# AutonoeGingerBread3.net
KiCad netlist of a schematic drawn in EAGLE
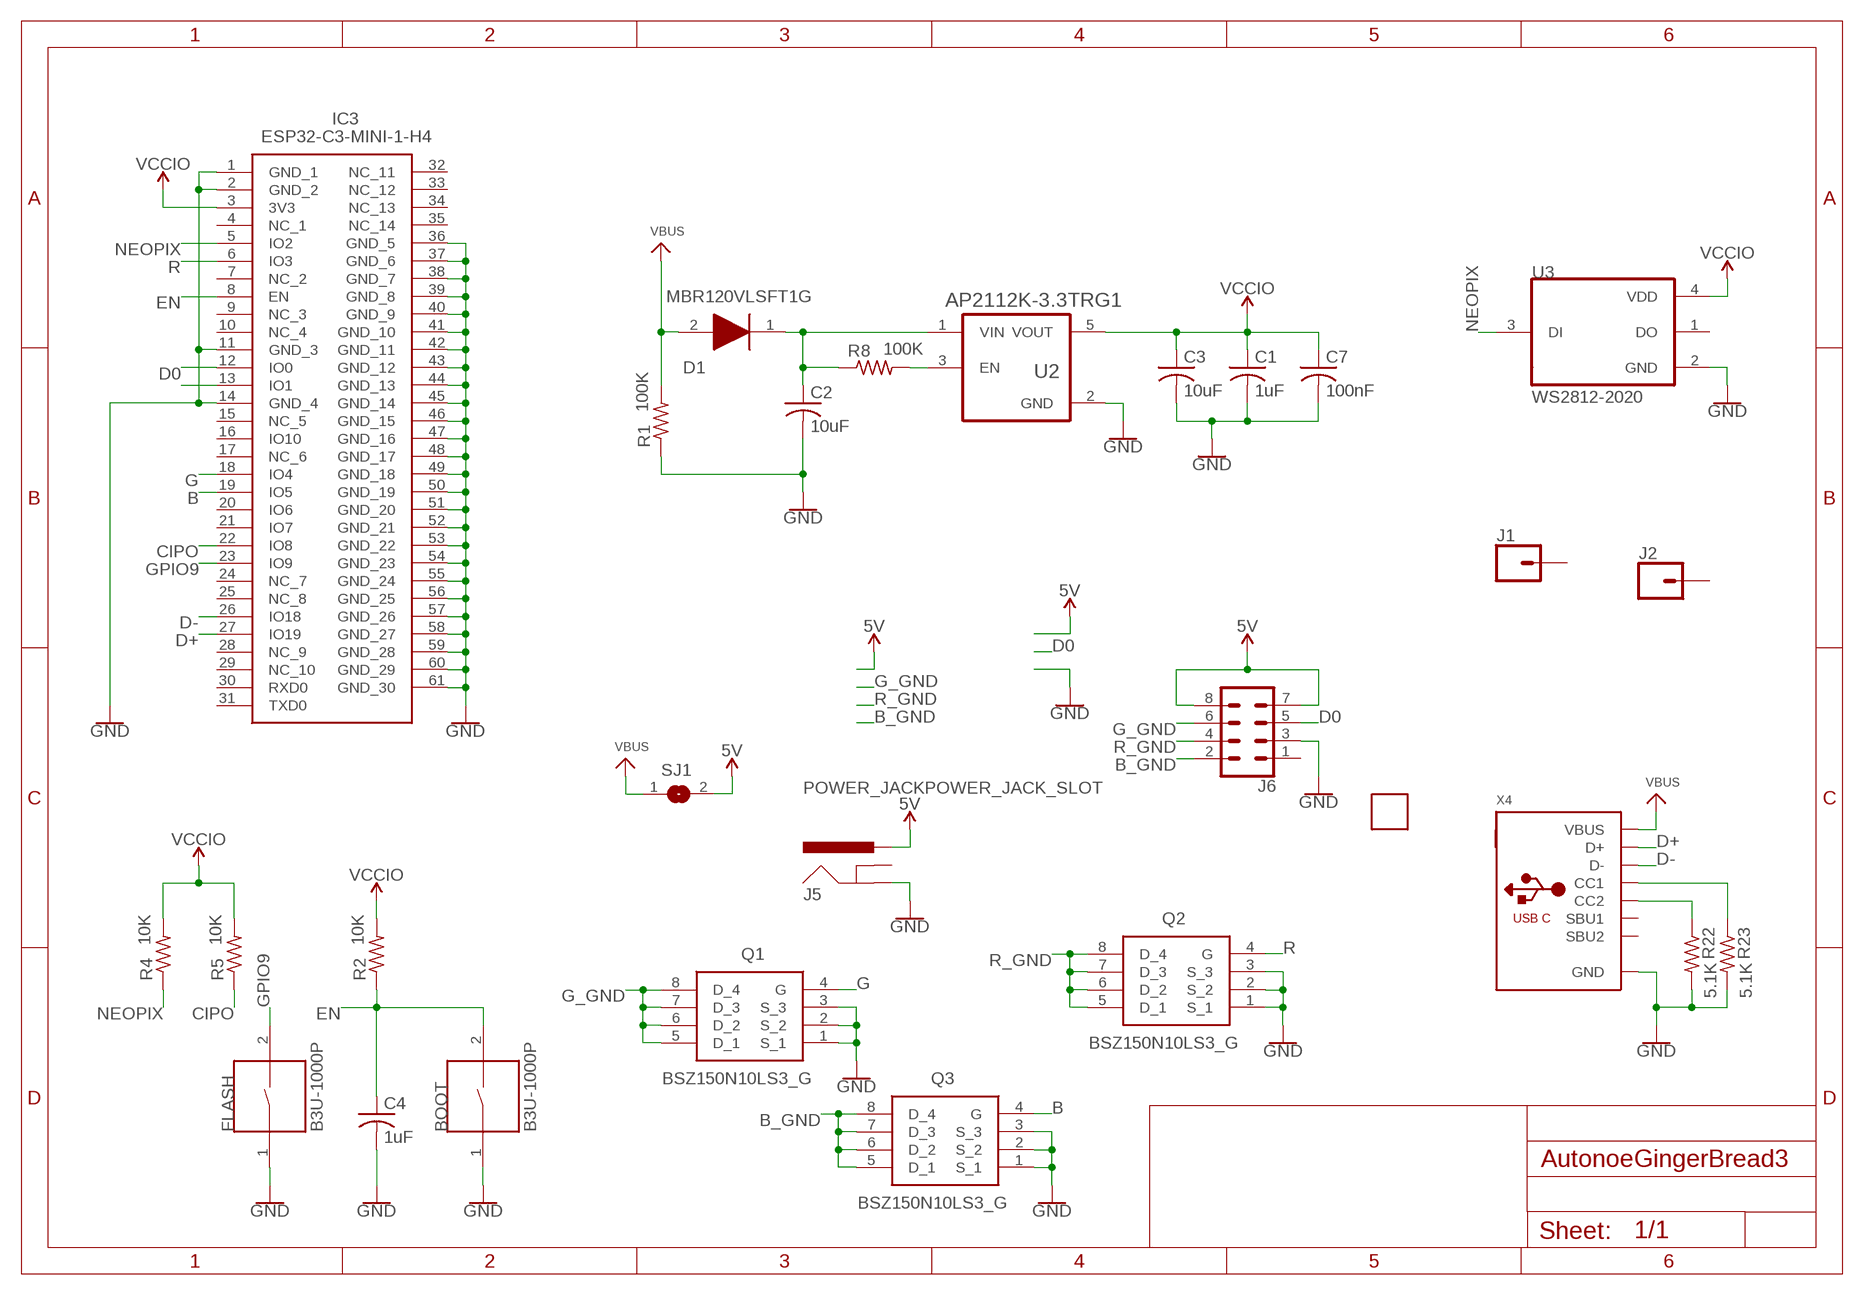
[diagram p0: schematic, sheet 1]

(export (version "E")
  (design (tool "Eeschema 10.0.6"))
  (components
    (comp (ref "BOOT")
      (value "B3U-1000P")
      (footprint "eagle-import:SW_B3U-1000P")
      (fields (field (name "MF") "Omron"))
      (libsource (lib "eagle-import") (part "B3U-1000P"))
    )
    (comp (ref "C1")
      (value "1uF")
      (footprint "eagle-import:C0402")
      (libsource (lib "eagle-import") (part "C-USC0402"))
    )
    (comp (ref "C2")
      (value "10uF")
      (footprint "eagle-import:C0402")
      (libsource (lib "eagle-import") (part "C-USC0402"))
    )
    (comp (ref "C3")
      (value "10uF")
      (footprint "eagle-import:C0402")
      (libsource (lib "eagle-import") (part "C-USC0402"))
    )
    (comp (ref "C4")
      (value "1uF")
      (footprint "eagle-import:C0402")
      (libsource (lib "eagle-import") (part "C-USC0402"))
    )
    (comp (ref "C7")
      (value "100nF")
      (footprint "eagle-import:C0402")
      (libsource (lib "eagle-import") (part "C-USC0402"))
    )
    (comp (ref "D1")
      (value "MBR120VLSFT1G")
      (footprint "eagle-import:SODFL3616X98N")
      (fields (field (name "MOUSER_PART_NUMBER") "863-MBR120VLSFT1G"))
      (libsource (lib "eagle-import") (part "MBR120VLSFT1G"))
    )
    (comp (ref "FLASH")
      (value "B3U-1000P")
      (footprint "eagle-import:SW_B3U-1000P")
      (fields (field (name "MF") "Omron"))
      (libsource (lib "eagle-import") (part "B3U-1000P"))
    )
    (comp (ref "IC3")
      (value "ESP32-C3-MINI-1-H4")
      (footprint "eagle-import:ESP32C3MINI1H4")
      (fields (field (name "MOUSER_PART_NUMBER") "356-ESP32-C3-MINI1H4"))
      (libsource (lib "eagle-import") (part "ESP32-C3-MINI-1-H4"))
    )
    (comp (ref "J1")
      (value "CONN_01PTH_2MM")
      (footprint "eagle-import:1X01_2MM")
      (libsource (lib "eagle-import") (part "CONN_01PTH_2MM"))
    )
    (comp (ref "J2")
      (value "CONN_01PTH_2MM")
      (footprint "eagle-import:1X01_2MM")
      (libsource (lib "eagle-import") (part "CONN_01PTH_2MM"))
    )
    (comp (ref "J5")
      (value "POWER_JACKPOWER_JACK_SLOT")
      (footprint "eagle-import:POWER_JACK_PTH_SLOT")
      (libsource (lib "eagle-import") (part "POWER_JACKPOWER_JACK_SLOT"))
    )
    (comp (ref "J6")
      (value "CONN_04X2")
      (footprint "eagle-import:2X4")
      (libsource (lib "eagle-import") (part "CONN_04X2"))
    )
    (comp (ref "Q1")
      (value "BSZ150N10LS3_G")
      (footprint "eagle-import:BSZ180P03NS3EGATMA1")
      (fields
        (field (name "MANUFACTURER_PART_NUMBER") "BSZ150N10LS3 G")
        (field (name "MOUSER_PART_NUMBER") "726-BSZ150N10LS3G")
      )
      (libsource (lib "eagle-import") (part "BSZ150N10LS3_G"))
    )
    (comp (ref "Q2")
      (value "BSZ150N10LS3_G")
      (footprint "eagle-import:BSZ180P03NS3EGATMA1")
      (fields
        (field (name "MANUFACTURER_PART_NUMBER") "BSZ150N10LS3 G")
        (field (name "MOUSER_PART_NUMBER") "726-BSZ150N10LS3G")
      )
      (libsource (lib "eagle-import") (part "BSZ150N10LS3_G"))
    )
    (comp (ref "Q3")
      (value "BSZ150N10LS3_G")
      (footprint "eagle-import:BSZ180P03NS3EGATMA1")
      (fields
        (field (name "MANUFACTURER_PART_NUMBER") "BSZ150N10LS3 G")
        (field (name "MOUSER_PART_NUMBER") "726-BSZ150N10LS3G")
      )
      (libsource (lib "eagle-import") (part "BSZ150N10LS3_G"))
    )
    (comp (ref "R1")
      (value "100K")
      (footprint "eagle-import:R0402")
      (libsource (lib "eagle-import") (part "R-US_R0402"))
    )
    (comp (ref "R2")
      (value "10K")
      (footprint "eagle-import:R0402")
      (libsource (lib "eagle-import") (part "R-US_R0402"))
    )
    (comp (ref "R4")
      (value "10K")
      (footprint "eagle-import:R0402")
      (libsource (lib "eagle-import") (part "R-US_R0402"))
    )
    (comp (ref "R5")
      (value "10K")
      (footprint "eagle-import:R0402")
      (libsource (lib "eagle-import") (part "R-US_R0402"))
    )
    (comp (ref "R8")
      (value "100K")
      (footprint "eagle-import:R0402")
      (libsource (lib "eagle-import") (part "R-US_R0402"))
    )
    (comp (ref "R22")
      (value "5.1K")
      (footprint "eagle-import:R0402")
      (libsource (lib "eagle-import") (part "R-US_R0402"))
    )
    (comp (ref "R23")
      (value "5.1K")
      (footprint "eagle-import:R0402")
      (libsource (lib "eagle-import") (part "R-US_R0402"))
    )
    (comp (ref "SJ1") (value "SJ") (footprint "eagle-import:SJ") (libsource (lib "eagle-import") (part "SJ")))
    (comp (ref "U$3")
      (value "SMARTT_SMALL")
      (footprint "eagle-import:SMARTT_SMALL")
      (libsource (lib "eagle-import") (part "SMARTT_SMALL"))
    )
    (comp (ref "U2")
      (value "AP2112K-3.3TRG1")
      (footprint "eagle-import:SOT95P285X140-5N")
      (fields (field (name "MF") "Diodes Inc."))
      (libsource (lib "eagle-import") (part "AP2112K-3.3TRG1"))
    )
    (comp (ref "U3")
      (value "WS2812-2020")
      (footprint "eagle-import:LED_WS2812-2020")
      (fields (field (name "MF") "Worldsemi"))
      (libsource (lib "eagle-import") (part "WS2812-2020"))
    )
    (comp (ref "X4")
      (value "MICROBUILDER_USB_C")
      (footprint "eagle-import:MICROBUILDER_USB_C_CUSB31-CFM2AX-01-X")
      (libsource (lib "eagle-import") (part "MICROBUILDER_USB_C"))
    )
  )
  (nets
    (net (code "1") (name "/B") (class "Default")
      (node (ref "IC3") (pin "19") (pinfunction "IO5_19") (pintype "bidirectional"))
      (node (ref "Q3") (pin "4") (pinfunction "G_4") (pintype "bidirectional"))
    )
    (net (code "2") (name "/B_GND") (class "Default")
      (node (ref "J6") (pin "2") (pinfunction "2_2") (pintype "passive"))
      (node (ref "Q3") (pin "5") (pinfunction "D_1_5") (pintype "bidirectional"))
      (node (ref "Q3") (pin "6") (pinfunction "D_2_6") (pintype "bidirectional"))
      (node (ref "Q3") (pin "7") (pinfunction "D_3_7") (pintype "bidirectional"))
      (node (ref "Q3") (pin "8") (pinfunction "D_4_8") (pintype "bidirectional"))
    )
    (net (code "3") (name "/CIPO") (class "Default")
      (node (ref "IC3") (pin "22") (pinfunction "IO8_22") (pintype "bidirectional"))
      (node (ref "R5") (pin "1") (pinfunction "1_1") (pintype "passive"))
    )
    (net (code "4") (name "/D+") (class "Default")
      (node (ref "IC3") (pin "27") (pinfunction "IO19_27") (pintype "bidirectional"))
      (node (ref "X4") (pin "A6") (pinfunction "D+_A6") (pintype "bidirectional"))
      (node (ref "X4") (pin "B6") (pinfunction "D+_B6") (pintype "bidirectional"))
    )
    (net (code "5") (name "/D-") (class "Default")
      (node (ref "IC3") (pin "26") (pinfunction "IO18_26") (pintype "bidirectional"))
      (node (ref "X4") (pin "A7") (pinfunction "D-_A7") (pintype "bidirectional"))
      (node (ref "X4") (pin "B7") (pinfunction "D-_B7") (pintype "bidirectional"))
    )
    (net (code "6") (name "/D0") (class "Default")
      (node (ref "IC3") (pin "12") (pinfunction "IO0_12") (pintype "bidirectional"))
      (node (ref "J6") (pin "5") (pinfunction "5_5") (pintype "passive"))
    )
    (net (code "7") (name "/EN") (class "Default")
      (node (ref "BOOT") (pin "2") (pinfunction "2_2") (pintype "passive"))
      (node (ref "C4") (pin "1") (pinfunction "1_1") (pintype "passive"))
      (node (ref "IC3") (pin "8") (pinfunction "EN_8") (pintype "bidirectional"))
      (node (ref "R2") (pin "1") (pinfunction "1_1") (pintype "passive"))
    )
    (net (code "8") (name "/G") (class "Default")
      (node (ref "IC3") (pin "18") (pinfunction "IO4_18") (pintype "bidirectional"))
      (node (ref "Q1") (pin "4") (pinfunction "G_4") (pintype "bidirectional"))
    )
    (net (code "9") (name "/GPIO9") (class "Default")
      (node (ref "FLASH") (pin "2") (pinfunction "2_2") (pintype "passive"))
      (node (ref "IC3") (pin "23") (pinfunction "IO9_23") (pintype "bidirectional"))
    )
    (net (code "10") (name "/G_GND") (class "Default")
      (node (ref "J6") (pin "6") (pinfunction "6_6") (pintype "passive"))
      (node (ref "Q1") (pin "5") (pinfunction "D_1_5") (pintype "bidirectional"))
      (node (ref "Q1") (pin "6") (pinfunction "D_2_6") (pintype "bidirectional"))
      (node (ref "Q1") (pin "7") (pinfunction "D_3_7") (pintype "bidirectional"))
      (node (ref "Q1") (pin "8") (pinfunction "D_4_8") (pintype "bidirectional"))
    )
    (net (code "11") (name "/NEOPIX") (class "Default")
      (node (ref "IC3") (pin "5") (pinfunction "IO2_5") (pintype "bidirectional"))
      (node (ref "R4") (pin "1") (pinfunction "1_1") (pintype "passive"))
      (node (ref "U3") (pin "3") (pinfunction "DI_3") (pintype "input"))
    )
    (net (code "12") (name "/R") (class "Default")
      (node (ref "IC3") (pin "6") (pinfunction "IO3_6") (pintype "bidirectional"))
      (node (ref "Q2") (pin "4") (pinfunction "G_4") (pintype "bidirectional"))
    )
    (net (code "13") (name "/R_GND") (class "Default")
      (node (ref "J6") (pin "4") (pinfunction "4_4") (pintype "passive"))
      (node (ref "Q2") (pin "5") (pinfunction "D_1_5") (pintype "bidirectional"))
      (node (ref "Q2") (pin "6") (pinfunction "D_2_6") (pintype "bidirectional"))
      (node (ref "Q2") (pin "7") (pinfunction "D_3_7") (pintype "bidirectional"))
      (node (ref "Q2") (pin "8") (pinfunction "D_4_8") (pintype "bidirectional"))
    )
    (net (code "14") (name "5V") (class "Default")
      (node (ref "J5") (pin "PWR") (pinfunction "PWR_PWR") (pintype "bidirectional"))
      (node (ref "J6") (pin "7") (pinfunction "7_7") (pintype "passive"))
      (node (ref "J6") (pin "8") (pinfunction "8_8") (pintype "passive"))
      (node (ref "SJ1") (pin "2") (pinfunction "2_2") (pintype "passive"))
    )
    (net (code "15") (name "GND") (class "Default")
      (node (ref "BOOT") (pin "1") (pinfunction "1_1") (pintype "passive"))
      (node (ref "C1") (pin "2") (pinfunction "2_2") (pintype "passive"))
      (node (ref "C2") (pin "2") (pinfunction "2_2") (pintype "passive"))
      (node (ref "C3") (pin "2") (pinfunction "2_2") (pintype "passive"))
      (node (ref "C4") (pin "2") (pinfunction "2_2") (pintype "passive"))
      (node (ref "C7") (pin "2") (pinfunction "2_2") (pintype "passive"))
      (node (ref "FLASH") (pin "1") (pinfunction "1_1") (pintype "passive"))
      (node (ref "IC3") (pin "1") (pinfunction "GND_1_1") (pintype "bidirectional"))
      (node (ref "IC3") (pin "11") (pinfunction "GND_3_11") (pintype "bidirectional"))
      (node (ref "IC3") (pin "14") (pinfunction "GND_4_14") (pintype "bidirectional"))
      (node (ref "IC3") (pin "2") (pinfunction "GND_2_2") (pintype "bidirectional"))
      (node (ref "IC3") (pin "36") (pinfunction "GND_5_36") (pintype "bidirectional"))
      (node (ref "IC3") (pin "37") (pinfunction "GND_6_37") (pintype "bidirectional"))
      (node (ref "IC3") (pin "38") (pinfunction "GND_7_38") (pintype "bidirectional"))
      (node (ref "IC3") (pin "39") (pinfunction "GND_8_39") (pintype "bidirectional"))
      (node (ref "IC3") (pin "40") (pinfunction "GND_9_40") (pintype "bidirectional"))
      (node (ref "IC3") (pin "41") (pinfunction "GND_10_41") (pintype "bidirectional"))
      (node (ref "IC3") (pin "42") (pinfunction "GND_11_42") (pintype "bidirectional"))
      (node (ref "IC3") (pin "43") (pinfunction "GND_12_43") (pintype "bidirectional"))
      (node (ref "IC3") (pin "44") (pinfunction "GND_13_44") (pintype "bidirectional"))
      (node (ref "IC3") (pin "45") (pinfunction "GND_14_45") (pintype "bidirectional"))
      (node (ref "IC3") (pin "46") (pinfunction "GND_15_46") (pintype "bidirectional"))
      (node (ref "IC3") (pin "47") (pinfunction "GND_16_47") (pintype "bidirectional"))
      (node (ref "IC3") (pin "48") (pinfunction "GND_17_48") (pintype "bidirectional"))
      (node (ref "IC3") (pin "49") (pinfunction "GND_18_49") (pintype "bidirectional"))
      (node (ref "IC3") (pin "50") (pinfunction "GND_19_50") (pintype "bidirectional"))
      (node (ref "IC3") (pin "51") (pinfunction "GND_20_51") (pintype "bidirectional"))
      (node (ref "IC3") (pin "52") (pinfunction "GND_21_52") (pintype "bidirectional"))
      (node (ref "IC3") (pin "53") (pinfunction "GND_22_53") (pintype "bidirectional"))
      (node (ref "IC3") (pin "54") (pinfunction "GND_23_54") (pintype "bidirectional"))
      (node (ref "IC3") (pin "55") (pinfunction "GND_24_55") (pintype "bidirectional"))
      (node (ref "IC3") (pin "56") (pinfunction "GND_25_56") (pintype "bidirectional"))
      (node (ref "IC3") (pin "57") (pinfunction "GND_26_57") (pintype "bidirectional"))
      (node (ref "IC3") (pin "58") (pinfunction "GND_27_58") (pintype "bidirectional"))
      (node (ref "IC3") (pin "59") (pinfunction "GND_28_59") (pintype "bidirectional"))
      (node (ref "IC3") (pin "60") (pinfunction "GND_29_60") (pintype "bidirectional"))
      (node (ref "IC3") (pin "61") (pinfunction "GND_30_61") (pintype "bidirectional"))
      (node (ref "J5") (pin "GND") (pinfunction "GND_GND") (pintype "bidirectional"))
      (node (ref "J6") (pin "3") (pinfunction "3_3") (pintype "passive"))
      (node (ref "Q1") (pin "1") (pinfunction "S_1_1") (pintype "bidirectional"))
      (node (ref "Q1") (pin "2") (pinfunction "S_2_2") (pintype "bidirectional"))
      (node (ref "Q1") (pin "3") (pinfunction "S_3_3") (pintype "bidirectional"))
      (node (ref "Q2") (pin "1") (pinfunction "S_1_1") (pintype "bidirectional"))
      (node (ref "Q2") (pin "2") (pinfunction "S_2_2") (pintype "bidirectional"))
      (node (ref "Q2") (pin "3") (pinfunction "S_3_3") (pintype "bidirectional"))
      (node (ref "Q3") (pin "1") (pinfunction "S_1_1") (pintype "bidirectional"))
      (node (ref "Q3") (pin "2") (pinfunction "S_2_2") (pintype "bidirectional"))
      (node (ref "Q3") (pin "3") (pinfunction "S_3_3") (pintype "bidirectional"))
      (node (ref "R1") (pin "1") (pinfunction "1_1") (pintype "passive"))
      (node (ref "R22") (pin "2") (pinfunction "2_2") (pintype "passive"))
      (node (ref "R23") (pin "2") (pinfunction "2_2") (pintype "passive"))
      (node (ref "U2") (pin "2") (pinfunction "GND_2") (pintype "power_in"))
      (node (ref "U3") (pin "2") (pinfunction "GND_2") (pintype "power_in"))
      (node (ref "X4") (pin "A1B12") (pinfunction "GND_A1B12") (pintype "power_in"))
      (node (ref "X4") (pin "B1A12") (pinfunction "GND_B1A12") (pintype "power_in"))
    )
    (net (code "16") (name "Net-(D1-K)") (class "Default")
      (node (ref "C2") (pin "1") (pinfunction "1_1") (pintype "passive"))
      (node (ref "D1") (pin "1") (pinfunction "K_1") (pintype "bidirectional"))
      (node (ref "R8") (pin "1") (pinfunction "1_1") (pintype "passive"))
      (node (ref "U2") (pin "1") (pinfunction "VIN_1") (pintype "power_in"))
    )
    (net (code "17") (name "Net-(U2-EN)") (class "Default")
      (node (ref "R8") (pin "2") (pinfunction "2_2") (pintype "passive"))
      (node (ref "U2") (pin "3") (pinfunction "EN_3") (pintype "input"))
    )
    (net (code "18") (name "Net-(X4-CC1)") (class "Default")
      (node (ref "R23") (pin "1") (pinfunction "1_1") (pintype "passive"))
      (node (ref "X4") (pin "A5") (pinfunction "CC1_A5") (pintype "bidirectional"))
    )
    (net (code "19") (name "Net-(X4-CC2)") (class "Default")
      (node (ref "R22") (pin "1") (pinfunction "1_1") (pintype "passive"))
      (node (ref "X4") (pin "B5") (pinfunction "CC2_B5") (pintype "bidirectional"))
    )
    (net (code "20") (name "VBUS") (class "Default")
      (node (ref "D1") (pin "2") (pinfunction "A_2") (pintype "bidirectional"))
      (node (ref "R1") (pin "2") (pinfunction "2_2") (pintype "passive"))
      (node (ref "SJ1") (pin "1") (pinfunction "1_1") (pintype "passive"))
      (node (ref "X4") (pin "A4B9") (pinfunction "VBUS_A4B9") (pintype "power_in"))
      (node (ref "X4") (pin "B4A9") (pinfunction "VBUS_B4A9") (pintype "power_in"))
    )
    (net (code "21") (name "VCCIO") (class "Default")
      (node (ref "C1") (pin "1") (pinfunction "1_1") (pintype "passive"))
      (node (ref "C3") (pin "1") (pinfunction "1_1") (pintype "passive"))
      (node (ref "C7") (pin "1") (pinfunction "1_1") (pintype "passive"))
      (node (ref "IC3") (pin "3") (pinfunction "3V3_3") (pintype "bidirectional"))
      (node (ref "R2") (pin "2") (pinfunction "2_2") (pintype "passive"))
      (node (ref "R4") (pin "2") (pinfunction "2_2") (pintype "passive"))
      (node (ref "R5") (pin "2") (pinfunction "2_2") (pintype "passive"))
      (node (ref "U2") (pin "5") (pinfunction "VOUT_5") (pintype "power_in"))
      (node (ref "U3") (pin "4") (pinfunction "VDD_4") (pintype "power_in"))
    )
    (net (code "22") (name "unconnected-(IC3-IO1-Pad13)") (class "Default")
      (node (ref "IC3") (pin "13") (pinfunction "IO1_13") (pintype "bidirectional"))
    )
    (net (code "23") (name "unconnected-(IC3-IO6-Pad20)") (class "Default")
      (node (ref "IC3") (pin "20") (pinfunction "IO6_20") (pintype "bidirectional"))
    )
    (net (code "24") (name "unconnected-(IC3-IO7-Pad21)") (class "Default")
      (node (ref "IC3") (pin "21") (pinfunction "IO7_21") (pintype "bidirectional"))
    )
    (net (code "25") (name "unconnected-(IC3-IO10-Pad16)") (class "Default")
      (node (ref "IC3") (pin "16") (pinfunction "IO10_16") (pintype "bidirectional"))
    )
    (net (code "26") (name "unconnected-(IC3-NC_1-Pad4)") (class "Default")
      (node (ref "IC3") (pin "4") (pinfunction "NC_1_4") (pintype "bidirectional"))
    )
    (net (code "27") (name "unconnected-(IC3-NC_2-Pad7)") (class "Default")
      (node (ref "IC3") (pin "7") (pinfunction "NC_2_7") (pintype "bidirectional"))
    )
    (net (code "28") (name "unconnected-(IC3-NC_3-Pad9)") (class "Default")
      (node (ref "IC3") (pin "9") (pinfunction "NC_3_9") (pintype "bidirectional"))
    )
    (net (code "29") (name "unconnected-(IC3-NC_4-Pad10)") (class "Default")
      (node (ref "IC3") (pin "10") (pinfunction "NC_4_10") (pintype "bidirectional"))
    )
    (net (code "30") (name "unconnected-(IC3-NC_5-Pad15)") (class "Default")
      (node (ref "IC3") (pin "15") (pinfunction "NC_5_15") (pintype "bidirectional"))
    )
    (net (code "31") (name "unconnected-(IC3-NC_6-Pad17)") (class "Default")
      (node (ref "IC3") (pin "17") (pinfunction "NC_6_17") (pintype "bidirectional"))
    )
    (net (code "32") (name "unconnected-(IC3-NC_7-Pad24)") (class "Default")
      (node (ref "IC3") (pin "24") (pinfunction "NC_7_24") (pintype "bidirectional"))
    )
    (net (code "33") (name "unconnected-(IC3-NC_8-Pad25)") (class "Default")
      (node (ref "IC3") (pin "25") (pinfunction "NC_8_25") (pintype "bidirectional"))
    )
    (net (code "34") (name "unconnected-(IC3-NC_9-Pad28)") (class "Default")
      (node (ref "IC3") (pin "28") (pinfunction "NC_9_28") (pintype "bidirectional"))
    )
    (net (code "35") (name "unconnected-(IC3-NC_10-Pad29)") (class "Default")
      (node (ref "IC3") (pin "29") (pinfunction "NC_10_29") (pintype "bidirectional"))
    )
    (net (code "36") (name "unconnected-(IC3-NC_11-Pad32)") (class "Default")
      (node (ref "IC3") (pin "32") (pinfunction "NC_11_32") (pintype "bidirectional"))
    )
    (net (code "37") (name "unconnected-(IC3-NC_12-Pad33)") (class "Default")
      (node (ref "IC3") (pin "33") (pinfunction "NC_12_33") (pintype "bidirectional"))
    )
    (net (code "38") (name "unconnected-(IC3-NC_13-Pad34)") (class "Default")
      (node (ref "IC3") (pin "34") (pinfunction "NC_13_34") (pintype "bidirectional"))
    )
    (net (code "39") (name "unconnected-(IC3-NC_14-Pad35)") (class "Default")
      (node (ref "IC3") (pin "35") (pinfunction "NC_14_35") (pintype "bidirectional"))
    )
    (net (code "40") (name "unconnected-(IC3-RXD0-Pad30)") (class "Default")
      (node (ref "IC3") (pin "30") (pinfunction "RXD0_30") (pintype "bidirectional"))
    )
    (net (code "41") (name "unconnected-(IC3-TXD0-Pad31)") (class "Default")
      (node (ref "IC3") (pin "31") (pinfunction "TXD0_31") (pintype "bidirectional"))
    )
    (net (code "42") (name "unconnected-(J1-Pad1)") (class "Default")
      (node (ref "J1") (pin "1") (pinfunction "1_1") (pintype "passive"))
    )
    (net (code "43") (name "unconnected-(J2-Pad1)") (class "Default")
      (node (ref "J2") (pin "1") (pinfunction "1_1") (pintype "passive"))
    )
    (net (code "44") (name "unconnected-(J5-PadGNDBREAK)") (class "Default")
      (node (ref "J5") (pin "GNDBREAK") (pinfunction "GNDBREAK_GNDBREAK") (pintype "bidirectional"))
    )
    (net (code "45") (name "unconnected-(J6-Pad1)") (class "Default")
      (node (ref "J6") (pin "1") (pinfunction "1_1") (pintype "passive"))
    )
    (net (code "46") (name "unconnected-(U3-DO-Pad1)") (class "Default")
      (node (ref "U3") (pin "1") (pinfunction "DO_1") (pintype "output"))
    )
    (net (code "47") (name "unconnected-(X4-SBU1-PadA8)") (class "Default")
      (node (ref "X4") (pin "A8") (pinfunction "SBU1_A8") (pintype "bidirectional"))
    )
    (net (code "48") (name "unconnected-(X4-SBU2-PadB8)") (class "Default")
      (node (ref "X4") (pin "B8") (pinfunction "SBU2_B8") (pintype "bidirectional"))
    )
  )
)
